# altium_hier_mcu.net
KiCad netlist of a schematic drawn in Altium Designer
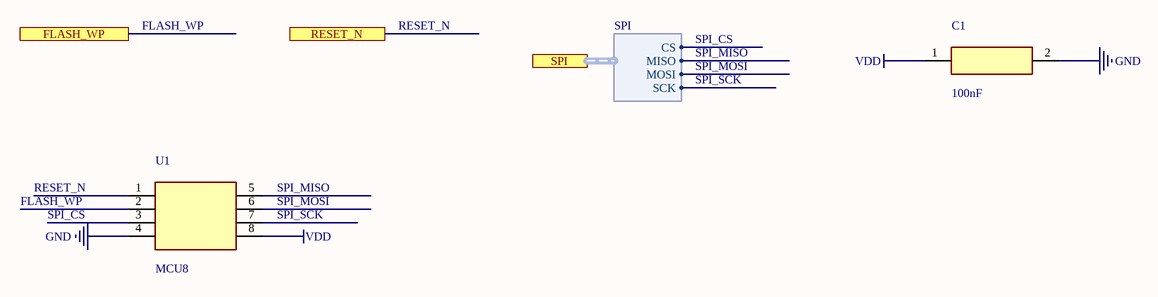
[diagram p0: altium_hier_mcu.SchDoc]

(export (version "E")
  (design (tool "Eeschema 10.0.6"))
  (components
    (comp (ref "C1")
      (value "100nF")
      (footprint "FenoliteHier:C0603")
      (libsource (lib "FenoliteHier") (part "CAP"))
    )
    (comp (ref "U1")
      (value "MCU8")
      (footprint "FenoliteHier:SOIC8")
      (libsource (lib "FenoliteHier") (part "MCU8"))
    )
  )
  (nets
    (net (code "2") (name "/FLASH_WP") (class "Default")
      (node (ref "U1") (pin "2") (pinfunction "2_2") (pintype "passive"))
    )
    (net (code "3") (name "/RESET_N") (class "Default")
      (node (ref "U1") (pin "1") (pinfunction "1_1") (pintype "passive"))
    )
    (net (code "4") (name "/SPI_CS") (class "Default")
      (node (ref "U1") (pin "3") (pinfunction "3_3") (pintype "passive"))
    )
    (net (code "5") (name "/SPI_MISO") (class "Default")
      (node (ref "U1") (pin "5") (pinfunction "5_5") (pintype "passive"))
    )
    (net (code "6") (name "/SPI_MOSI") (class "Default")
      (node (ref "U1") (pin "6") (pinfunction "6_6") (pintype "passive"))
    )
    (net (code "7") (name "/SPI_SCK") (class "Default")
      (node (ref "U1") (pin "7") (pinfunction "7_7") (pintype "passive"))
    )
    (net (code "9") (name "GND") (class "Default")
      (node (ref "C1") (pin "2") (pinfunction "2_2") (pintype "passive"))
      (node (ref "U1") (pin "4") (pinfunction "4_4") (pintype "passive"))
    )
    (net (code "10") (name "VDD") (class "Default")
      (node (ref "C1") (pin "1") (pinfunction "1_1") (pintype "passive"))
      (node (ref "U1") (pin "8") (pinfunction "8_8") (pintype "passive"))
    )
  )
)
